# RADIO.net
KiCad netlist of a schematic drawn in EAGLE
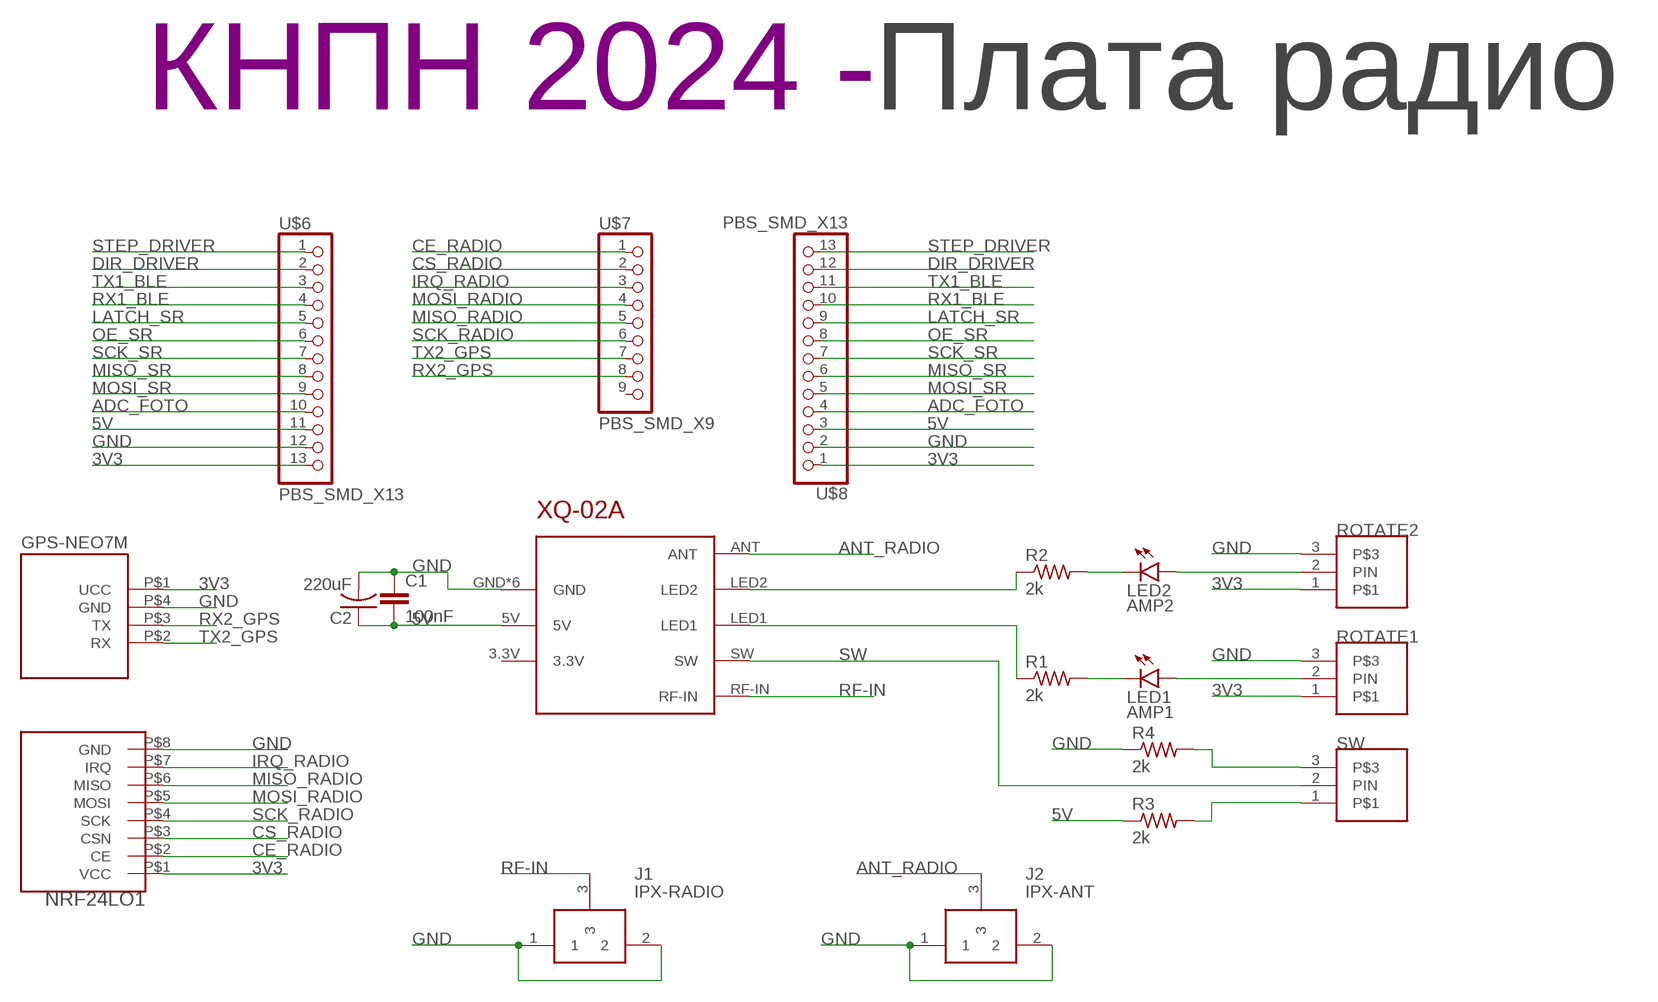
[diagram p0: schematic, sheet 1]

(export (version "E")
  (design (tool "Eeschema 10.0.6"))
  (components
    (comp (ref "C1")
      (value "100nF")
      (footprint "eagle-import:C0603")
      (libsource (lib "eagle-import") (part "C-EUC0603"))
    )
    (comp (ref "C2")
      (value "220uF")
      (footprint "eagle-import:ECAP220-CMD")
      (libsource (lib "eagle-import") (part "ECAPECAP220"))
    )
    (comp (ref "GPS-NEO7M")
      (value "GPS-NEO7M")
      (footprint "eagle-import:GPS-NEO7M")
      (libsource (lib "eagle-import") (part "GPS-NEO7M"))
    )
    (comp (ref "J1")
      (value "IPX-RADIO")
      (footprint "eagle-import:U.FL-R-SMT-1(10)")
      (fields
        (field (name "ARROW_PART_NUMBER") "U.FL-R-SMT-1(10)")
        (field (name "MOUSER_PART_NUMBER") "798-U.FL-R-SMT-110")
      )
      (libsource (lib "eagle-import") (part "U.FL-R-SMT-1_10_"))
    )
    (comp (ref "J2")
      (value "IPX-ANT")
      (footprint "eagle-import:U.FL-R-SMT-1(10)")
      (fields
        (field (name "ARROW_PART_NUMBER") "U.FL-R-SMT-1(10)")
        (field (name "MOUSER_PART_NUMBER") "798-U.FL-R-SMT-110")
      )
      (libsource (lib "eagle-import") (part "U.FL-R-SMT-1_10_"))
    )
    (comp (ref "LED1")
      (value "AMP1")
      (footprint "eagle-import:CHIPLED_0603")
      (libsource (lib "eagle-import") (part "LEDCHIPLED_0603"))
    )
    (comp (ref "LED2")
      (value "AMP2")
      (footprint "eagle-import:CHIPLED_0603")
      (libsource (lib "eagle-import") (part "LEDCHIPLED_0603"))
    )
    (comp (ref "NRF24LO1")
      (value "NRF24L01_ML01SP4")
      (footprint "eagle-import:NRF24L01_ML01SP4")
      (libsource (lib "eagle-import") (part "NRF24L01_ML01SP4"))
    )
    (comp (ref "R1")
      (value "2k")
      (footprint "eagle-import:R0603")
      (libsource (lib "eagle-import") (part "R-US_R0603"))
    )
    (comp (ref "R2")
      (value "2k")
      (footprint "eagle-import:R0603")
      (libsource (lib "eagle-import") (part "R-US_R0603"))
    )
    (comp (ref "R3")
      (value "2k")
      (footprint "eagle-import:R0603")
      (libsource (lib "eagle-import") (part "R-US_R0603"))
    )
    (comp (ref "R4")
      (value "2k")
      (footprint "eagle-import:R0603")
      (libsource (lib "eagle-import") (part "R-US_R0603"))
    )
    (comp (ref "ROTATE1")
      (value "CONNECT_3")
      (footprint "eagle-import:CONNECT_3")
      (libsource (lib "eagle-import") (part "CONNECT_3"))
    )
    (comp (ref "ROTATE2")
      (value "CONNECT_3")
      (footprint "eagle-import:CONNECT_3")
      (libsource (lib "eagle-import") (part "CONNECT_3"))
    )
    (comp (ref "SW")
      (value "CONNECT_3")
      (footprint "eagle-import:CONNECT_3")
      (libsource (lib "eagle-import") (part "CONNECT_3"))
    )
    (comp (ref "U$1")
      (value "Плата радио")
      (footprint "eagle-import:LOGO")
      (libsource (lib "eagle-import") (part "LOGOPCB-{dblquote}{dblquote}"))
    )
    (comp (ref "U$6")
      (value "PBS_SMD_X13")
      (footprint "eagle-import:PBD_SMD_X13")
      (libsource (lib "eagle-import") (part "PBS_SMD_X13"))
    )
    (comp (ref "U$7")
      (value "PBS_SMD_X9")
      (footprint "eagle-import:PBS_SMD_X9")
      (libsource (lib "eagle-import") (part "PBS_SMD_X9"))
    )
    (comp (ref "U$8")
      (value "PBS_SMD_X13")
      (footprint "eagle-import:PBD_SMD_X13")
      (libsource (lib "eagle-import") (part "PBS_SMD_X13"))
    )
    (comp (ref "XQ-02A")
      (value "XQ-02A")
      (footprint "eagle-import:XQ-02A")
      (libsource (lib "eagle-import") (part "XQ-02A"))
    )
  )
  (nets
    (net (code "1") (name "/3V3") (class "Default")
      (node (ref "GPS-NEO7M") (pin "P$1") (pinfunction "UCC_P$1") (pintype "bidirectional"))
      (node (ref "NRF24LO1") (pin "P$1") (pinfunction "VCC_P$1") (pintype "bidirectional"))
      (node (ref "ROTATE1") (pin "1") (pinfunction "P$1_1") (pintype "bidirectional"))
      (node (ref "ROTATE2") (pin "1") (pinfunction "P$1_1") (pintype "bidirectional"))
      (node (ref "U$6") (pin "13") (pinfunction "13_13") (pintype "passive"))
      (node (ref "U$8") (pin "1") (pinfunction "1_1") (pintype "passive"))
    )
    (net (code "2") (name "/5V") (class "Default")
      (node (ref "C1") (pin "2") (pinfunction "2_2") (pintype "passive"))
      (node (ref "C2") (pin "P$1") (pinfunction "1_P$1") (pintype "passive"))
      (node (ref "R3") (pin "1") (pinfunction "1_1") (pintype "passive"))
      (node (ref "U$6") (pin "11") (pinfunction "11_11") (pintype "passive"))
      (node (ref "U$8") (pin "3") (pinfunction "3_3") (pintype "passive"))
      (node (ref "XQ-02A") (pin "5V") (pinfunction "5V_5V") (pintype "bidirectional"))
    )
    (net (code "3") (name "/ADC_FOTO") (class "Default")
      (node (ref "U$6") (pin "10") (pinfunction "10_10") (pintype "passive"))
      (node (ref "U$8") (pin "4") (pinfunction "4_4") (pintype "passive"))
    )
    (net (code "4") (name "/ANT_RADIO") (class "Default")
      (node (ref "J2") (pin "3") (pinfunction "3_3") (pintype "bidirectional"))
      (node (ref "XQ-02A") (pin "ANT") (pinfunction "ANT_ANT") (pintype "bidirectional"))
    )
    (net (code "5") (name "/CE_RADIO") (class "Default")
      (node (ref "NRF24LO1") (pin "P$2") (pinfunction "CE_P$2") (pintype "bidirectional"))
      (node (ref "U$7") (pin "1") (pinfunction "1_1") (pintype "passive"))
    )
    (net (code "6") (name "/CS_RADIO") (class "Default")
      (node (ref "NRF24LO1") (pin "P$3") (pinfunction "CSN_P$3") (pintype "bidirectional"))
      (node (ref "U$7") (pin "2") (pinfunction "2_2") (pintype "passive"))
    )
    (net (code "7") (name "/DIR_DRIVER") (class "Default")
      (node (ref "U$6") (pin "2") (pinfunction "2_2") (pintype "passive"))
      (node (ref "U$8") (pin "12") (pinfunction "12_12") (pintype "passive"))
    )
    (net (code "8") (name "/GND") (class "Default")
      (node (ref "C1") (pin "1") (pinfunction "1_1") (pintype "passive"))
      (node (ref "C2") (pin "P$2") (pinfunction "2_P$2") (pintype "passive"))
      (node (ref "GPS-NEO7M") (pin "P$4") (pinfunction "GND_P$4") (pintype "bidirectional"))
      (node (ref "J1") (pin "1") (pinfunction "1_1") (pintype "bidirectional"))
      (node (ref "J1") (pin "2") (pinfunction "2_2") (pintype "bidirectional"))
      (node (ref "J2") (pin "1") (pinfunction "1_1") (pintype "bidirectional"))
      (node (ref "J2") (pin "2") (pinfunction "2_2") (pintype "bidirectional"))
      (node (ref "NRF24LO1") (pin "P$8") (pinfunction "GND_P$8") (pintype "bidirectional"))
      (node (ref "R4") (pin "1") (pinfunction "1_1") (pintype "passive"))
      (node (ref "ROTATE1") (pin "3") (pinfunction "P$3_3") (pintype "bidirectional"))
      (node (ref "ROTATE2") (pin "3") (pinfunction "P$3_3") (pintype "bidirectional"))
      (node (ref "U$6") (pin "12") (pinfunction "12_12") (pintype "passive"))
      (node (ref "U$8") (pin "2") (pinfunction "2_2") (pintype "passive"))
      (node (ref "XQ-02A") (pin "GND") (pinfunction "GND_GND") (pintype "bidirectional"))
      (node (ref "XQ-02A") (pin "GND1") (pinfunction "GND_GND1") (pintype "bidirectional"))
      (node (ref "XQ-02A") (pin "GND2") (pinfunction "GND_GND2") (pintype "bidirectional"))
      (node (ref "XQ-02A") (pin "GND3") (pinfunction "GND_GND3") (pintype "bidirectional"))
      (node (ref "XQ-02A") (pin "GND4") (pinfunction "GND_GND4") (pintype "bidirectional"))
      (node (ref "XQ-02A") (pin "GND5") (pinfunction "GND_GND5") (pintype "bidirectional"))
    )
    (net (code "9") (name "/IRQ_RADIO") (class "Default")
      (node (ref "NRF24LO1") (pin "P$7") (pinfunction "IRQ_P$7") (pintype "bidirectional"))
      (node (ref "U$7") (pin "3") (pinfunction "3_3") (pintype "passive"))
    )
    (net (code "10") (name "/LATCH_SR") (class "Default")
      (node (ref "U$6") (pin "5") (pinfunction "5_5") (pintype "passive"))
      (node (ref "U$8") (pin "9") (pinfunction "9_9") (pintype "passive"))
    )
    (net (code "11") (name "/MISO_RADIO") (class "Default")
      (node (ref "NRF24LO1") (pin "P$6") (pinfunction "MISO_P$6") (pintype "bidirectional"))
      (node (ref "U$7") (pin "5") (pinfunction "5_5") (pintype "passive"))
    )
    (net (code "12") (name "/MISO_SR") (class "Default")
      (node (ref "U$6") (pin "8") (pinfunction "8_8") (pintype "passive"))
      (node (ref "U$8") (pin "6") (pinfunction "6_6") (pintype "passive"))
    )
    (net (code "13") (name "/MOSI_RADIO") (class "Default")
      (node (ref "NRF24LO1") (pin "P$5") (pinfunction "MOSI_P$5") (pintype "bidirectional"))
      (node (ref "U$7") (pin "4") (pinfunction "4_4") (pintype "passive"))
    )
    (net (code "14") (name "/MOSI_SR") (class "Default")
      (node (ref "U$6") (pin "9") (pinfunction "9_9") (pintype "passive"))
      (node (ref "U$8") (pin "5") (pinfunction "5_5") (pintype "passive"))
    )
    (net (code "15") (name "/OE_SR") (class "Default")
      (node (ref "U$6") (pin "6") (pinfunction "6_6") (pintype "passive"))
      (node (ref "U$8") (pin "8") (pinfunction "8_8") (pintype "passive"))
    )
    (net (code "16") (name "/RF-IN") (class "Default")
      (node (ref "J1") (pin "3") (pinfunction "3_3") (pintype "bidirectional"))
      (node (ref "XQ-02A") (pin "RF-IN") (pinfunction "RF-IN_RF-IN") (pintype "bidirectional"))
    )
    (net (code "17") (name "/RX1_BLE") (class "Default")
      (node (ref "U$6") (pin "4") (pinfunction "4_4") (pintype "passive"))
      (node (ref "U$8") (pin "10") (pinfunction "10_10") (pintype "passive"))
    )
    (net (code "18") (name "/RX2_GPS") (class "Default")
      (node (ref "GPS-NEO7M") (pin "P$3") (pinfunction "TX_P$3") (pintype "bidirectional"))
      (node (ref "U$7") (pin "8") (pinfunction "8_8") (pintype "passive"))
    )
    (net (code "19") (name "/SCK_RADIO") (class "Default")
      (node (ref "NRF24LO1") (pin "P$4") (pinfunction "SCK_P$4") (pintype "bidirectional"))
      (node (ref "U$7") (pin "6") (pinfunction "6_6") (pintype "passive"))
    )
    (net (code "20") (name "/SCK_SR") (class "Default")
      (node (ref "U$6") (pin "7") (pinfunction "7_7") (pintype "passive"))
      (node (ref "U$8") (pin "7") (pinfunction "7_7") (pintype "passive"))
    )
    (net (code "21") (name "/STEP_DRIVER") (class "Default")
      (node (ref "U$6") (pin "1") (pinfunction "1_1") (pintype "passive"))
      (node (ref "U$8") (pin "13") (pinfunction "13_13") (pintype "passive"))
    )
    (net (code "22") (name "/SW") (class "Default")
      (node (ref "SW") (pin "2") (pinfunction "PIN_2") (pintype "bidirectional"))
      (node (ref "XQ-02A") (pin "SW") (pinfunction "SW_SW") (pintype "bidirectional"))
    )
    (net (code "23") (name "/TX1_BLE") (class "Default")
      (node (ref "U$6") (pin "3") (pinfunction "3_3") (pintype "passive"))
      (node (ref "U$8") (pin "11") (pinfunction "11_11") (pintype "passive"))
    )
    (net (code "24") (name "/TX2_GPS") (class "Default")
      (node (ref "GPS-NEO7M") (pin "P$2") (pinfunction "RX_P$2") (pintype "bidirectional"))
      (node (ref "U$7") (pin "7") (pinfunction "7_7") (pintype "passive"))
    )
    (net (code "25") (name "Net-(LED1-PadC)") (class "Default")
      (node (ref "LED1") (pin "C") (pinfunction "C_C") (pintype "passive"))
      (node (ref "R1") (pin "2") (pinfunction "2_2") (pintype "passive"))
    )
    (net (code "26") (name "Net-(LED2-PadC)") (class "Default")
      (node (ref "LED2") (pin "C") (pinfunction "C_C") (pintype "passive"))
      (node (ref "R2") (pin "2") (pinfunction "2_2") (pintype "passive"))
    )
    (net (code "27") (name "Net-(R1-Pad1)") (class "Default")
      (node (ref "R1") (pin "1") (pinfunction "1_1") (pintype "passive"))
      (node (ref "XQ-02A") (pin "LED1") (pinfunction "LED1_LED1") (pintype "bidirectional"))
    )
    (net (code "28") (name "Net-(R2-Pad1)") (class "Default")
      (node (ref "R2") (pin "1") (pinfunction "1_1") (pintype "passive"))
      (node (ref "XQ-02A") (pin "LED2") (pinfunction "LED2_LED2") (pintype "bidirectional"))
    )
    (net (code "29") (name "Net-(ROTATE1-PIN)") (class "Default")
      (node (ref "LED1") (pin "A") (pinfunction "A_A") (pintype "passive"))
      (node (ref "ROTATE1") (pin "2") (pinfunction "PIN_2") (pintype "bidirectional"))
    )
    (net (code "30") (name "Net-(ROTATE2-PIN)") (class "Default")
      (node (ref "LED2") (pin "A") (pinfunction "A_A") (pintype "passive"))
      (node (ref "ROTATE2") (pin "2") (pinfunction "PIN_2") (pintype "bidirectional"))
    )
    (net (code "31") (name "Net-(SW-P$1)") (class "Default")
      (node (ref "R3") (pin "2") (pinfunction "2_2") (pintype "passive"))
      (node (ref "SW") (pin "1") (pinfunction "P$1_1") (pintype "bidirectional"))
    )
    (net (code "32") (name "Net-(SW-P$3)") (class "Default")
      (node (ref "R4") (pin "2") (pinfunction "2_2") (pintype "passive"))
      (node (ref "SW") (pin "3") (pinfunction "P$3_3") (pintype "bidirectional"))
    )
    (net (code "33") (name "unconnected-(U$7-Pad9)") (class "Default")
      (node (ref "U$7") (pin "9") (pinfunction "9_9") (pintype "passive"))
    )
    (net (code "34") (name "unconnected-(XQ-02A-Pad3.3V)") (class "Default")
      (node (ref "XQ-02A") (pin "3.3V") (pinfunction "3.3V_3.3V") (pintype "bidirectional"))
    )
  )
)
